# POWER.net
KiCad netlist of a schematic drawn in Altium Designer
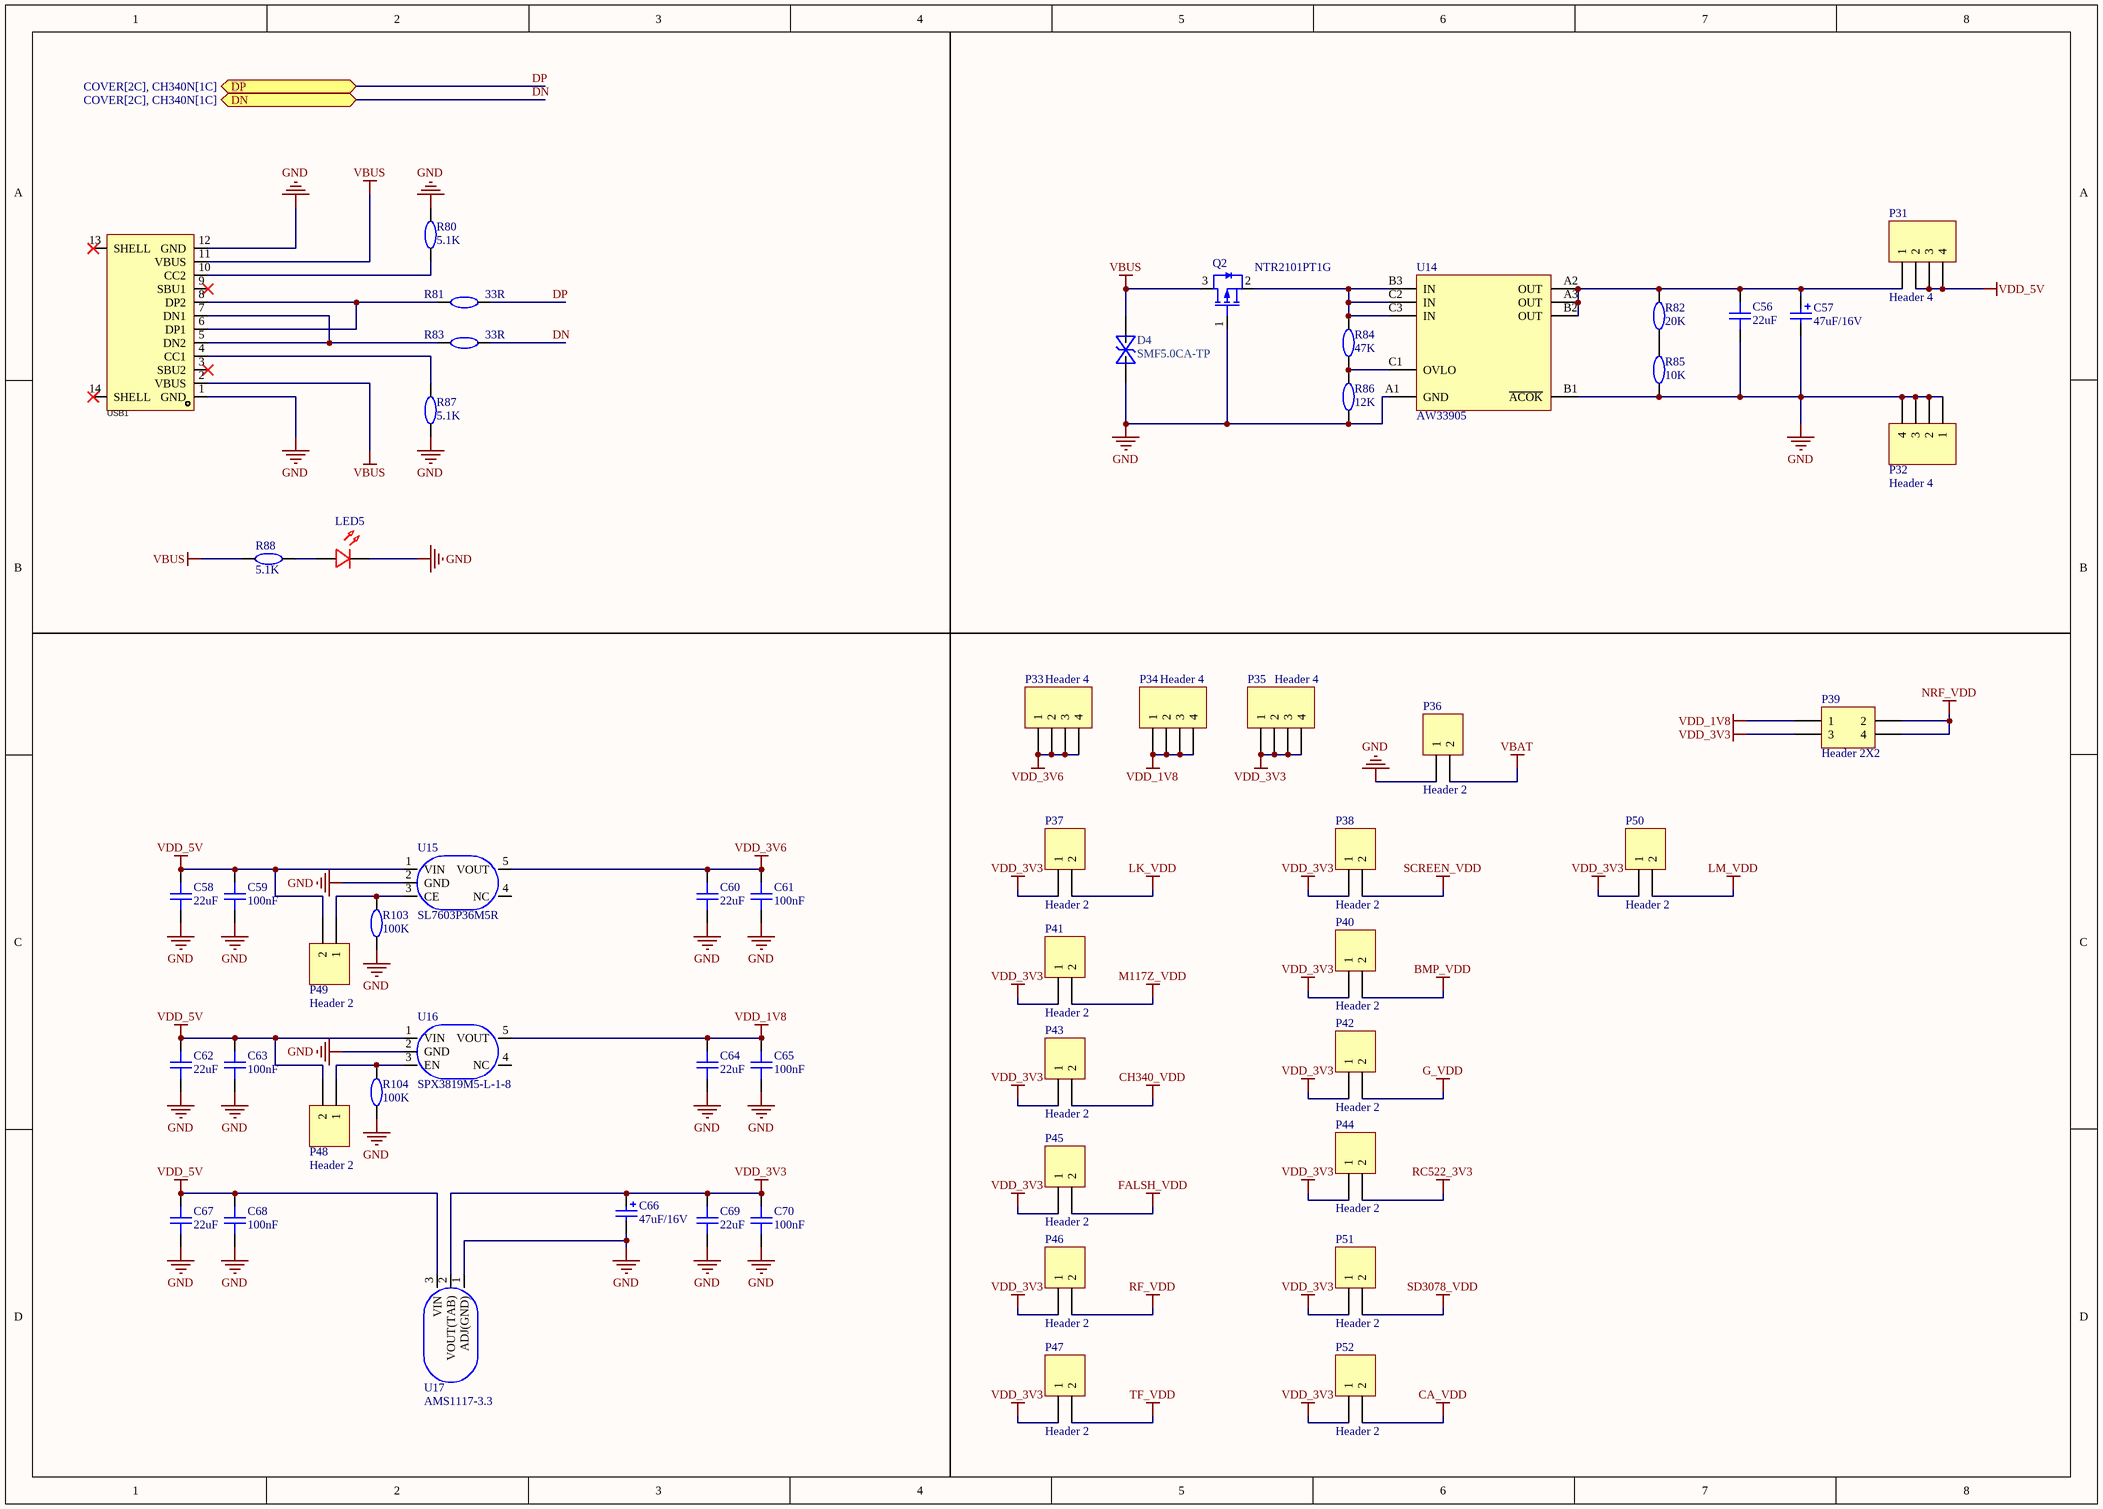
[diagram p0: POWER.SchDoc]

(export (version "E")
  (design (tool "Eeschema 10.0.6"))
  (components
    (comp (ref "C56")
      (value "22uF")
      (footprint "C0603")
      (fields (field (name "NAME") "22uF"))
      (libsource (lib "my_library") (part "CAP_0603"))
    )
    (comp (ref "C57")
      (value "47uF/16V")
      (footprint "CASE-B_3528")
      (description "J  Polarized Capacitor 有极性电容")
      (fields (field (name "PUBLISHER") "Altium Limited"))
      (libsource (lib "my_library") (part "Cap_CASE_B_3528"))
    )
    (comp (ref "C58")
      (value "22uF")
      (footprint "C0603")
      (fields (field (name "NAME") "22uF"))
      (libsource (lib "my_library") (part "CAP_0603"))
    )
    (comp (ref "C59")
      (value "100nF")
      (footprint "C0402")
      (fields (field (name "NAME") "100nF"))
      (libsource (lib "my_library") (part "CAP_0402"))
    )
    (comp (ref "C60")
      (value "22uF")
      (footprint "C0603")
      (fields (field (name "NAME") "22uF"))
      (libsource (lib "my_library") (part "CAP_0603"))
    )
    (comp (ref "C61")
      (value "100nF")
      (footprint "C0402")
      (fields (field (name "NAME") "100nF"))
      (libsource (lib "my_library") (part "CAP_0402"))
    )
    (comp (ref "C62")
      (value "22uF")
      (footprint "C0603")
      (fields (field (name "NAME") "22uF"))
      (libsource (lib "my_library") (part "CAP_0603"))
    )
    (comp (ref "C63")
      (value "100nF")
      (footprint "C0402")
      (fields (field (name "NAME") "100nF"))
      (libsource (lib "my_library") (part "CAP_0402"))
    )
    (comp (ref "C64")
      (value "22uF")
      (footprint "C0603")
      (fields (field (name "NAME") "22uF"))
      (libsource (lib "my_library") (part "CAP_0603"))
    )
    (comp (ref "C65")
      (value "100nF")
      (footprint "C0402")
      (fields (field (name "NAME") "100nF"))
      (libsource (lib "my_library") (part "CAP_0402"))
    )
    (comp (ref "C66")
      (value "47uF/16V")
      (footprint "CASE-B_3528")
      (description "J  Polarized Capacitor 有极性电容")
      (fields (field (name "PUBLISHER") "Altium Limited"))
      (libsource (lib "my_library") (part "Cap_CASE_B_3528"))
    )
    (comp (ref "C67")
      (value "22uF")
      (footprint "C0603")
      (fields (field (name "NAME") "22uF"))
      (libsource (lib "my_library") (part "CAP_0603"))
    )
    (comp (ref "C68")
      (value "100nF")
      (footprint "C0402")
      (fields (field (name "NAME") "100nF"))
      (libsource (lib "my_library") (part "CAP_0402"))
    )
    (comp (ref "C69")
      (value "22uF")
      (footprint "C0603")
      (fields (field (name "NAME") "22uF"))
      (libsource (lib "my_library") (part "CAP_0603"))
    )
    (comp (ref "C70")
      (value "100nF")
      (footprint "C0402")
      (fields (field (name "NAME") "100nF"))
      (libsource (lib "my_library") (part "CAP_0402"))
    )
    (comp (ref "D4")
      (value "SMF5.0CA-TP")
      (footprint "SOD-123FL_L2.8-W1.7-LS3.6")
      (description "C914432")
      (fields (field (name "MANUFACTURER") "MCC(美微科)"))
      (libsource (lib "my_library") (part "SMF5.0CA-TP"))
    )
    (comp (ref "LED5")
      (value "LED_0603-R")
      (footprint "LED_0603")
      (libsource (lib "my_library") (part "LED_0603-R"))
    )
    (comp (ref "P31")
      (value "Header 4")
      (footprint "HDR1X4")
      (description "Header, 4-Pin")
      (fields (field (name "PUBLISHER") "Altium Limited"))
      (libsource (lib "Miscellaneous Connectors") (part "Header 4"))
    )
    (comp (ref "P32")
      (value "Header 4")
      (footprint "HDR1X4")
      (description "Header, 4-Pin")
      (fields (field (name "PUBLISHER") "Altium Limited"))
      (libsource (lib "") (part "Header 4_1"))
    )
    (comp (ref "P33")
      (value "Header 4")
      (footprint "HDR1X4")
      (description "Header, 4-Pin")
      (fields (field (name "PUBLISHER") "Altium Limited"))
      (libsource (lib "Miscellaneous Connectors") (part "Header 4"))
    )
    (comp (ref "P34")
      (value "Header 4")
      (footprint "HDR1X4")
      (description "Header, 4-Pin")
      (fields (field (name "PUBLISHER") "Altium Limited"))
      (libsource (lib "Miscellaneous Connectors") (part "Header 4"))
    )
    (comp (ref "P35")
      (value "Header 4")
      (footprint "HDR1X4")
      (description "Header, 4-Pin")
      (fields (field (name "PUBLISHER") "Altium Limited"))
      (libsource (lib "Miscellaneous Connectors") (part "Header 4"))
    )
    (comp (ref "P36")
      (value "Header 2")
      (footprint "HDR1X2")
      (description "Header, 2-Pin")
      (fields (field (name "PUBLISHER") "Altium Limited"))
      (libsource (lib "") (part "Header 2_1"))
    )
    (comp (ref "P37")
      (value "Header 2")
      (footprint "HDR1X2")
      (description "Header, 2-Pin")
      (fields (field (name "PUBLISHER") "Altium Limited"))
      (libsource (lib "") (part "Header 2_1"))
    )
    (comp (ref "P38")
      (value "Header 2")
      (footprint "HDR1X2")
      (description "Header, 2-Pin")
      (fields (field (name "PUBLISHER") "Altium Limited"))
      (libsource (lib "") (part "Header 2_1"))
    )
    (comp (ref "P39")
      (value "Header 2X2")
      (footprint "HDR2X2")
      (description "Header, 2-Pin, Dual row")
      (fields (field (name "PUBLISHER") "Altium Limited"))
      (libsource (lib "Miscellaneous Connectors") (part "Header 2X2"))
    )
    (comp (ref "P40")
      (value "Header 2")
      (footprint "HDR1X2")
      (description "Header, 2-Pin")
      (fields (field (name "PUBLISHER") "Altium Limited"))
      (libsource (lib "") (part "Header 2_1"))
    )
    (comp (ref "P41")
      (value "Header 2")
      (footprint "HDR1X2")
      (description "Header, 2-Pin")
      (fields (field (name "PUBLISHER") "Altium Limited"))
      (libsource (lib "") (part "Header 2_1"))
    )
    (comp (ref "P42")
      (value "Header 2")
      (footprint "HDR1X2")
      (description "Header, 2-Pin")
      (fields (field (name "PUBLISHER") "Altium Limited"))
      (libsource (lib "") (part "Header 2_1"))
    )
    (comp (ref "P43")
      (value "Header 2")
      (footprint "HDR1X2")
      (description "Header, 2-Pin")
      (fields (field (name "PUBLISHER") "Altium Limited"))
      (libsource (lib "") (part "Header 2_1"))
    )
    (comp (ref "P44")
      (value "Header 2")
      (footprint "HDR1X2")
      (description "Header, 2-Pin")
      (fields (field (name "PUBLISHER") "Altium Limited"))
      (libsource (lib "") (part "Header 2_1"))
    )
    (comp (ref "P45")
      (value "Header 2")
      (footprint "HDR1X2")
      (description "Header, 2-Pin")
      (fields (field (name "PUBLISHER") "Altium Limited"))
      (libsource (lib "") (part "Header 2_1"))
    )
    (comp (ref "P46")
      (value "Header 2")
      (footprint "HDR1X2")
      (description "Header, 2-Pin")
      (fields (field (name "PUBLISHER") "Altium Limited"))
      (libsource (lib "") (part "Header 2_1"))
    )
    (comp (ref "P47")
      (value "Header 2")
      (footprint "HDR1X2")
      (description "Header, 2-Pin")
      (fields (field (name "PUBLISHER") "Altium Limited"))
      (libsource (lib "") (part "Header 2_1"))
    )
    (comp (ref "P48")
      (value "Header 2")
      (footprint "HDR1X2")
      (description "Header, 2-Pin")
      (fields (field (name "PUBLISHER") "Altium Limited"))
      (libsource (lib "Miscellaneous Connectors") (part "Header 2"))
    )
    (comp (ref "P49")
      (value "Header 2")
      (footprint "HDR1X2")
      (description "Header, 2-Pin")
      (fields (field (name "PUBLISHER") "Altium Limited"))
      (libsource (lib "Miscellaneous Connectors") (part "Header 2"))
    )
    (comp (ref "P50")
      (value "Header 2")
      (footprint "HDR1X2")
      (description "Header, 2-Pin")
      (fields (field (name "PUBLISHER") "Altium Limited"))
      (libsource (lib "") (part "Header 2_1"))
    )
    (comp (ref "P51")
      (value "Header 2")
      (footprint "HDR1X2")
      (description "Header, 2-Pin")
      (fields (field (name "PUBLISHER") "Altium Limited"))
      (libsource (lib "") (part "Header 2_1"))
    )
    (comp (ref "P52")
      (value "Header 2")
      (footprint "HDR1X2")
      (description "Header, 2-Pin")
      (fields (field (name "PUBLISHER") "Altium Limited"))
      (libsource (lib "") (part "Header 2_1"))
    )
    (comp (ref "Q2")
      (value "NTR2101PT1G")
      (footprint "SOT-23(SOT-23-3)")
      (description "J  MOS(场效应管)P道沟  二极管 C168745")
      (libsource (lib "my_library") (part "NTR2101PT1G"))
    )
    (comp (ref "R80")
      (value "5.1K")
      (footprint "R0402")
      (fields (field (name "NAME") "5.1K"))
      (libsource (lib "my_library") (part "Res_0402"))
    )
    (comp (ref "R81")
      (value "33R")
      (footprint "R0402")
      (fields (field (name "NAME") "33R"))
      (libsource (lib "my_library") (part "Res_0402"))
    )
    (comp (ref "R82")
      (value "20K")
      (footprint "R0402")
      (fields (field (name "NAME") "20K"))
      (libsource (lib "my_library") (part "Res_0402"))
    )
    (comp (ref "R83")
      (value "33R")
      (footprint "R0402")
      (fields (field (name "NAME") "33R"))
      (libsource (lib "my_library") (part "Res_0402"))
    )
    (comp (ref "R84")
      (value "47K")
      (footprint "R0402")
      (fields (field (name "NAME") "47K"))
      (libsource (lib "my_library") (part "Res_0402"))
    )
    (comp (ref "R85")
      (value "10K")
      (footprint "R0402")
      (fields (field (name "NAME") "10K"))
      (libsource (lib "my_library") (part "Res_0402"))
    )
    (comp (ref "R86")
      (value "12K")
      (footprint "R0402")
      (fields (field (name "NAME") "12K"))
      (libsource (lib "my_library") (part "Res_0402"))
    )
    (comp (ref "R87")
      (value "5.1K")
      (footprint "R0402")
      (fields (field (name "NAME") "5.1K"))
      (libsource (lib "my_library") (part "Res_0402"))
    )
    (comp (ref "R88")
      (value "5.1K")
      (footprint "R0402")
      (fields (field (name "NAME") "5.1K"))
      (libsource (lib "my_library") (part "Res_0402"))
    )
    (comp (ref "R103")
      (value "100K")
      (footprint "R0402")
      (fields (field (name "NAME") "100K"))
      (libsource (lib "my_library") (part "Res_0402"))
    )
    (comp (ref "R104")
      (value "100K")
      (footprint "R0402")
      (fields (field (name "NAME") "100K"))
      (libsource (lib "my_library") (part "Res_0402"))
    )
    (comp (ref "U14")
      (value "AW33905")
      (footprint "DSBGA-9_L1.2-W1.2-R3-C3-P0.40-BL")
      (description "C401024")
      (libsource (lib "my_library") (part "AW33905"))
    )
    (comp (ref "U15")
      (value "SL7603P36M5R")
      (footprint "SOT-23-5_L3.0-W1.7-P0.95-LS2.8-BL")
      (fields (field (name "MANUFACTURER") "Slkor(萨科微)") (field (name "NAME") "SL7603P36M5R"))
      (libsource (lib "my_library") (part "SL7603P36M5R"))
    )
    (comp (ref "U16")
      (value "SPX3819M5-L-1-8")
      (footprint "SOT-23-5_L3.0-W1.7-P0.95-LS2.8-BL")
      (fields (field (name "MANUFACTURER") "TECH PUBLIC(台舟)") (field (name "NAME") "SPX3819M5-L-1-8"))
      (libsource (lib "my_library") (part "SPX3819M5-L-1-8"))
    )
    (comp (ref "U17")
      (value "AMS1117-3.3")
      (footprint "SOT-89_L4.5-W2.5-P1.50-LS4.2-BR")
      (fields (field (name "MANUFACTURER") "UMW(友台半导体)") (field (name "NAME") "AMS1117-3.3"))
      (libsource (lib "my_library") (part "AMS1117-3.3_C347256"))
    )
    (comp (ref "USB1")
      (value "TYPE-C 16PIN 2MD(073)")
      (footprint "USB-C-SMD_TYPE-C-6PIN-2MD-073")
      (description "C2765186")
      (fields (field (name "MANUFACTURER") "SHOU HAN(首韩)"))
      (libsource (lib "my_library") (part "TYPE-C 16PIN 2MD(073)"))
    )
  )
  (nets
    (net (code "1") (name "/DN") (class "Default")
      (node (ref "R83") (pin "1") (pinfunction "1_1") (pintype "passive"))
    )
    (net (code "2") (name "/DP") (class "Default")
      (node (ref "R81") (pin "1") (pinfunction "1_1") (pintype "passive"))
    )
    (net (code "3") (name "BMP_VDD") (class "Default")
      (node (ref "P40") (pin "2") (pinfunction "2_2") (pintype "passive"))
    )
    (net (code "4") (name "CA_VDD") (class "Default")
      (node (ref "P52") (pin "2") (pinfunction "2_2") (pintype "passive"))
    )
    (net (code "5") (name "CH340_VDD") (class "Default")
      (node (ref "P43") (pin "2") (pinfunction "2_2") (pintype "passive"))
    )
    (net (code "6") (name "FALSH_VDD") (class "Default")
      (node (ref "P45") (pin "2") (pinfunction "2_2") (pintype "passive"))
    )
    (net (code "7") (name "GND") (class "Default")
      (node (ref "C56") (pin "1") (pinfunction "1_1") (pintype "passive"))
      (node (ref "C57") (pin "2") (pinfunction "2_2") (pintype "passive"))
      (node (ref "C58") (pin "1") (pinfunction "1_1") (pintype "passive"))
      (node (ref "C59") (pin "1") (pinfunction "1_1") (pintype "passive"))
      (node (ref "C60") (pin "1") (pinfunction "1_1") (pintype "passive"))
      (node (ref "C61") (pin "1") (pinfunction "1_1") (pintype "passive"))
      (node (ref "C62") (pin "1") (pinfunction "1_1") (pintype "passive"))
      (node (ref "C63") (pin "1") (pinfunction "1_1") (pintype "passive"))
      (node (ref "C64") (pin "1") (pinfunction "1_1") (pintype "passive"))
      (node (ref "C65") (pin "1") (pinfunction "1_1") (pintype "passive"))
      (node (ref "C66") (pin "2") (pinfunction "2_2") (pintype "passive"))
      (node (ref "C67") (pin "1") (pinfunction "1_1") (pintype "passive"))
      (node (ref "C68") (pin "1") (pinfunction "1_1") (pintype "passive"))
      (node (ref "C69") (pin "1") (pinfunction "1_1") (pintype "passive"))
      (node (ref "C70") (pin "1") (pinfunction "1_1") (pintype "passive"))
      (node (ref "D4") (pin "1") (pinfunction "1_1") (pintype "passive"))
      (node (ref "LED5") (pin "1") (pinfunction "C_1") (pintype "passive"))
      (node (ref "P32") (pin "1") (pinfunction "1_1") (pintype "passive"))
      (node (ref "P32") (pin "2") (pinfunction "2_2") (pintype "passive"))
      (node (ref "P32") (pin "3") (pinfunction "3_3") (pintype "passive"))
      (node (ref "P32") (pin "4") (pinfunction "4_4") (pintype "passive"))
      (node (ref "P36") (pin "1") (pinfunction "1_1") (pintype "passive"))
      (node (ref "Q2") (pin "1") (pinfunction "G_1") (pintype "passive"))
      (node (ref "R103") (pin "1") (pinfunction "1_1") (pintype "passive"))
      (node (ref "R104") (pin "1") (pinfunction "1_1") (pintype "passive"))
      (node (ref "R80") (pin "2") (pinfunction "2_2") (pintype "passive"))
      (node (ref "R85") (pin "1") (pinfunction "1_1") (pintype "passive"))
      (node (ref "R86") (pin "1") (pinfunction "1_1") (pintype "passive"))
      (node (ref "R87") (pin "1") (pinfunction "1_1") (pintype "passive"))
      (node (ref "U14") (pin "A1") (pinfunction "GND_A1") (pintype "passive"))
      (node (ref "U14") (pin "B1") (pinfunction "~{ACOK}_B1") (pintype "passive"))
      (node (ref "U15") (pin "2") (pinfunction "GND_2") (pintype "passive"))
      (node (ref "U16") (pin "2") (pinfunction "GND_2") (pintype "passive"))
      (node (ref "U17") (pin "1") (pinfunction "ADJ(GND)_1") (pintype "passive"))
      (node (ref "USB1") (pin "1") (pinfunction "GND_1") (pintype "passive"))
      (node (ref "USB1") (pin "12") (pinfunction "GND_12") (pintype "passive"))
    )
    (net (code "8") (name "G_VDD") (class "Default")
      (node (ref "P42") (pin "2") (pinfunction "2_2") (pintype "passive"))
    )
    (net (code "9") (name "LK_VDD") (class "Default")
      (node (ref "P37") (pin "2") (pinfunction "2_2") (pintype "passive"))
    )
    (net (code "10") (name "LM_VDD") (class "Default")
      (node (ref "P50") (pin "2") (pinfunction "2_2") (pintype "passive"))
    )
    (net (code "11") (name "M117Z_VDD") (class "Default")
      (node (ref "P41") (pin "2") (pinfunction "2_2") (pintype "passive"))
    )
    (net (code "12") (name "NRF_VDD") (class "Default")
      (node (ref "P39") (pin "2") (pinfunction "2_2") (pintype "passive"))
      (node (ref "P39") (pin "4") (pinfunction "4_4") (pintype "passive"))
    )
    (net (code "13") (name "Net-(C56-Pad2)") (class "Default")
      (node (ref "C56") (pin "2") (pinfunction "2_2") (pintype "passive"))
      (node (ref "C57") (pin "1") (pinfunction "1_1") (pintype "passive"))
      (node (ref "P31") (pin "1") (pinfunction "1_1") (pintype "passive"))
      (node (ref "R82") (pin "2") (pinfunction "2_2") (pintype "passive"))
      (node (ref "U14") (pin "A2") (pinfunction "OUT_A2") (pintype "passive"))
      (node (ref "U14") (pin "A3") (pinfunction "OUT_A3") (pintype "passive"))
      (node (ref "U14") (pin "B2") (pinfunction "OUT_B2") (pintype "passive"))
    )
    (net (code "14") (name "Net-(LED5-A)") (class "Default")
      (node (ref "LED5") (pin "2") (pinfunction "A_2") (pintype "passive"))
      (node (ref "R88") (pin "1") (pinfunction "1_1") (pintype "passive"))
    )
    (net (code "15") (name "Net-(Q2-S)") (class "Default")
      (node (ref "Q2") (pin "2") (pinfunction "S_2") (pintype "passive"))
      (node (ref "R84") (pin "2") (pinfunction "2_2") (pintype "passive"))
      (node (ref "U14") (pin "B3") (pinfunction "IN_B3") (pintype "passive"))
      (node (ref "U14") (pin "C2") (pinfunction "IN_C2") (pintype "passive"))
      (node (ref "U14") (pin "C3") (pinfunction "IN_C3") (pintype "passive"))
    )
    (net (code "16") (name "Net-(R82-Pad1)") (class "Default")
      (node (ref "R82") (pin "1") (pinfunction "1_1") (pintype "passive"))
      (node (ref "R85") (pin "2") (pinfunction "2_2") (pintype "passive"))
    )
    (net (code "17") (name "Net-(U14-OVLO)") (class "Default")
      (node (ref "R84") (pin "1") (pinfunction "1_1") (pintype "passive"))
      (node (ref "R86") (pin "2") (pinfunction "2_2") (pintype "passive"))
      (node (ref "U14") (pin "C1") (pinfunction "OVLO_C1") (pintype "passive"))
    )
    (net (code "18") (name "Net-(U15-CE)") (class "Default")
      (node (ref "P49") (pin "1") (pinfunction "1_1") (pintype "passive"))
      (node (ref "R103") (pin "2") (pinfunction "2_2") (pintype "passive"))
      (node (ref "U15") (pin "3") (pinfunction "CE_3") (pintype "passive"))
    )
    (net (code "19") (name "Net-(U16-EN)") (class "Default")
      (node (ref "P48") (pin "1") (pinfunction "1_1") (pintype "passive"))
      (node (ref "R104") (pin "2") (pinfunction "2_2") (pintype "passive"))
      (node (ref "U16") (pin "3") (pinfunction "EN_3") (pintype "passive"))
    )
    (net (code "20") (name "Net-(USB1-CC1)") (class "Default")
      (node (ref "R87") (pin "2") (pinfunction "2_2") (pintype "passive"))
      (node (ref "USB1") (pin "4") (pinfunction "CC1_4") (pintype "passive"))
    )
    (net (code "21") (name "Net-(USB1-CC2)") (class "Default")
      (node (ref "R80") (pin "1") (pinfunction "1_1") (pintype "passive"))
      (node (ref "USB1") (pin "10") (pinfunction "CC2_10") (pintype "passive"))
    )
    (net (code "22") (name "Net-(USB1-DN1)") (class "Default")
      (node (ref "R83") (pin "2") (pinfunction "2_2") (pintype "passive"))
      (node (ref "USB1") (pin "5") (pinfunction "DN2_5") (pintype "passive"))
      (node (ref "USB1") (pin "7") (pinfunction "DN1_7") (pintype "passive"))
    )
    (net (code "23") (name "Net-(USB1-DP1)") (class "Default")
      (node (ref "R81") (pin "2") (pinfunction "2_2") (pintype "passive"))
      (node (ref "USB1") (pin "6") (pinfunction "DP1_6") (pintype "passive"))
      (node (ref "USB1") (pin "8") (pinfunction "DP2_8") (pintype "passive"))
    )
    (net (code "24") (name "RC522_3V3") (class "Default")
      (node (ref "P44") (pin "2") (pinfunction "2_2") (pintype "passive"))
    )
    (net (code "25") (name "RF_VDD") (class "Default")
      (node (ref "P46") (pin "2") (pinfunction "2_2") (pintype "passive"))
    )
    (net (code "26") (name "SCREEN_VDD") (class "Default")
      (node (ref "P38") (pin "2") (pinfunction "2_2") (pintype "passive"))
    )
    (net (code "27") (name "SD3078_VDD") (class "Default")
      (node (ref "P51") (pin "2") (pinfunction "2_2") (pintype "passive"))
    )
    (net (code "28") (name "TF_VDD") (class "Default")
      (node (ref "P47") (pin "2") (pinfunction "2_2") (pintype "passive"))
    )
    (net (code "29") (name "VBAT") (class "Default")
      (node (ref "P36") (pin "2") (pinfunction "2_2") (pintype "passive"))
    )
    (net (code "30") (name "VBUS") (class "Default")
      (node (ref "D4") (pin "2") (pinfunction "2_2") (pintype "passive"))
      (node (ref "Q2") (pin "3") (pinfunction "D_3") (pintype "passive"))
      (node (ref "R88") (pin "2") (pinfunction "2_2") (pintype "passive"))
      (node (ref "USB1") (pin "11") (pinfunction "VBUS_11") (pintype "passive"))
      (node (ref "USB1") (pin "2") (pinfunction "VBUS_2") (pintype "passive"))
    )
    (net (code "31") (name "VDD_1V8") (class "Default")
      (node (ref "C64") (pin "2") (pinfunction "2_2") (pintype "passive"))
      (node (ref "C65") (pin "2") (pinfunction "2_2") (pintype "passive"))
      (node (ref "P34") (pin "1") (pinfunction "1_1") (pintype "passive"))
      (node (ref "P34") (pin "2") (pinfunction "2_2") (pintype "passive"))
      (node (ref "P34") (pin "3") (pinfunction "3_3") (pintype "passive"))
      (node (ref "P34") (pin "4") (pinfunction "4_4") (pintype "passive"))
      (node (ref "P39") (pin "1") (pinfunction "1_1") (pintype "passive"))
      (node (ref "U16") (pin "5") (pinfunction "VOUT_5") (pintype "passive"))
    )
    (net (code "32") (name "VDD_3V3") (class "Default")
      (node (ref "C66") (pin "1") (pinfunction "1_1") (pintype "passive"))
      (node (ref "C69") (pin "2") (pinfunction "2_2") (pintype "passive"))
      (node (ref "C70") (pin "2") (pinfunction "2_2") (pintype "passive"))
      (node (ref "P35") (pin "1") (pinfunction "1_1") (pintype "passive"))
      (node (ref "P35") (pin "2") (pinfunction "2_2") (pintype "passive"))
      (node (ref "P35") (pin "3") (pinfunction "3_3") (pintype "passive"))
      (node (ref "P35") (pin "4") (pinfunction "4_4") (pintype "passive"))
      (node (ref "P37") (pin "1") (pinfunction "1_1") (pintype "passive"))
      (node (ref "P38") (pin "1") (pinfunction "1_1") (pintype "passive"))
      (node (ref "P39") (pin "3") (pinfunction "3_3") (pintype "passive"))
      (node (ref "P40") (pin "1") (pinfunction "1_1") (pintype "passive"))
      (node (ref "P41") (pin "1") (pinfunction "1_1") (pintype "passive"))
      (node (ref "P42") (pin "1") (pinfunction "1_1") (pintype "passive"))
      (node (ref "P43") (pin "1") (pinfunction "1_1") (pintype "passive"))
      (node (ref "P44") (pin "1") (pinfunction "1_1") (pintype "passive"))
      (node (ref "P45") (pin "1") (pinfunction "1_1") (pintype "passive"))
      (node (ref "P46") (pin "1") (pinfunction "1_1") (pintype "passive"))
      (node (ref "P47") (pin "1") (pinfunction "1_1") (pintype "passive"))
      (node (ref "P50") (pin "1") (pinfunction "1_1") (pintype "passive"))
      (node (ref "P51") (pin "1") (pinfunction "1_1") (pintype "passive"))
      (node (ref "P52") (pin "1") (pinfunction "1_1") (pintype "passive"))
      (node (ref "U17") (pin "2") (pinfunction "VOUT(TAB)_2") (pintype "passive"))
    )
    (net (code "33") (name "VDD_3V6") (class "Default")
      (node (ref "C60") (pin "2") (pinfunction "2_2") (pintype "passive"))
      (node (ref "C61") (pin "2") (pinfunction "2_2") (pintype "passive"))
      (node (ref "P33") (pin "1") (pinfunction "1_1") (pintype "passive"))
      (node (ref "P33") (pin "2") (pinfunction "2_2") (pintype "passive"))
      (node (ref "P33") (pin "3") (pinfunction "3_3") (pintype "passive"))
      (node (ref "P33") (pin "4") (pinfunction "4_4") (pintype "passive"))
      (node (ref "U15") (pin "5") (pinfunction "VOUT_5") (pintype "passive"))
    )
    (net (code "34") (name "VDD_5V") (class "Default")
      (node (ref "C58") (pin "2") (pinfunction "2_2") (pintype "passive"))
      (node (ref "C59") (pin "2") (pinfunction "2_2") (pintype "passive"))
      (node (ref "C62") (pin "2") (pinfunction "2_2") (pintype "passive"))
      (node (ref "C63") (pin "2") (pinfunction "2_2") (pintype "passive"))
      (node (ref "C67") (pin "2") (pinfunction "2_2") (pintype "passive"))
      (node (ref "C68") (pin "2") (pinfunction "2_2") (pintype "passive"))
      (node (ref "P31") (pin "2") (pinfunction "2_2") (pintype "passive"))
      (node (ref "P31") (pin "3") (pinfunction "3_3") (pintype "passive"))
      (node (ref "P31") (pin "4") (pinfunction "4_4") (pintype "passive"))
      (node (ref "P48") (pin "2") (pinfunction "2_2") (pintype "passive"))
      (node (ref "P49") (pin "2") (pinfunction "2_2") (pintype "passive"))
      (node (ref "U15") (pin "1") (pinfunction "VIN_1") (pintype "passive"))
      (node (ref "U16") (pin "1") (pinfunction "VIN_1") (pintype "passive"))
      (node (ref "U17") (pin "3") (pinfunction "VIN_3") (pintype "passive"))
    )
    (net (code "35") (name "unconnected-(U15-NC-Pad4)") (class "Default")
      (node (ref "U15") (pin "4") (pinfunction "NC_4") (pintype "passive"))
    )
    (net (code "36") (name "unconnected-(U16-NC-Pad4)") (class "Default")
      (node (ref "U16") (pin "4") (pinfunction "NC_4") (pintype "passive"))
    )
    (net (code "37") (name "unconnected-(USB1-SBU1-Pad9)") (class "Default")
      (node (ref "USB1") (pin "9") (pinfunction "SBU1_9") (pintype "passive+no_connect"))
    )
    (net (code "38") (name "unconnected-(USB1-SBU2-Pad3)") (class "Default")
      (node (ref "USB1") (pin "3") (pinfunction "SBU2_3") (pintype "passive+no_connect"))
    )
    (net (code "39") (name "unconnected-(USB1-SHELL-Pad13)") (class "Default")
      (node (ref "USB1") (pin "13") (pinfunction "SHELL_13") (pintype "passive+no_connect"))
    )
    (net (code "40") (name "unconnected-(USB1-SHELL-Pad14)") (class "Default")
      (node (ref "USB1") (pin "14") (pinfunction "SHELL_14") (pintype "passive+no_connect"))
    )
  )
)
